# SH_IR_V1_0.net
KiCad netlist of a schematic drawn in Altium Designer
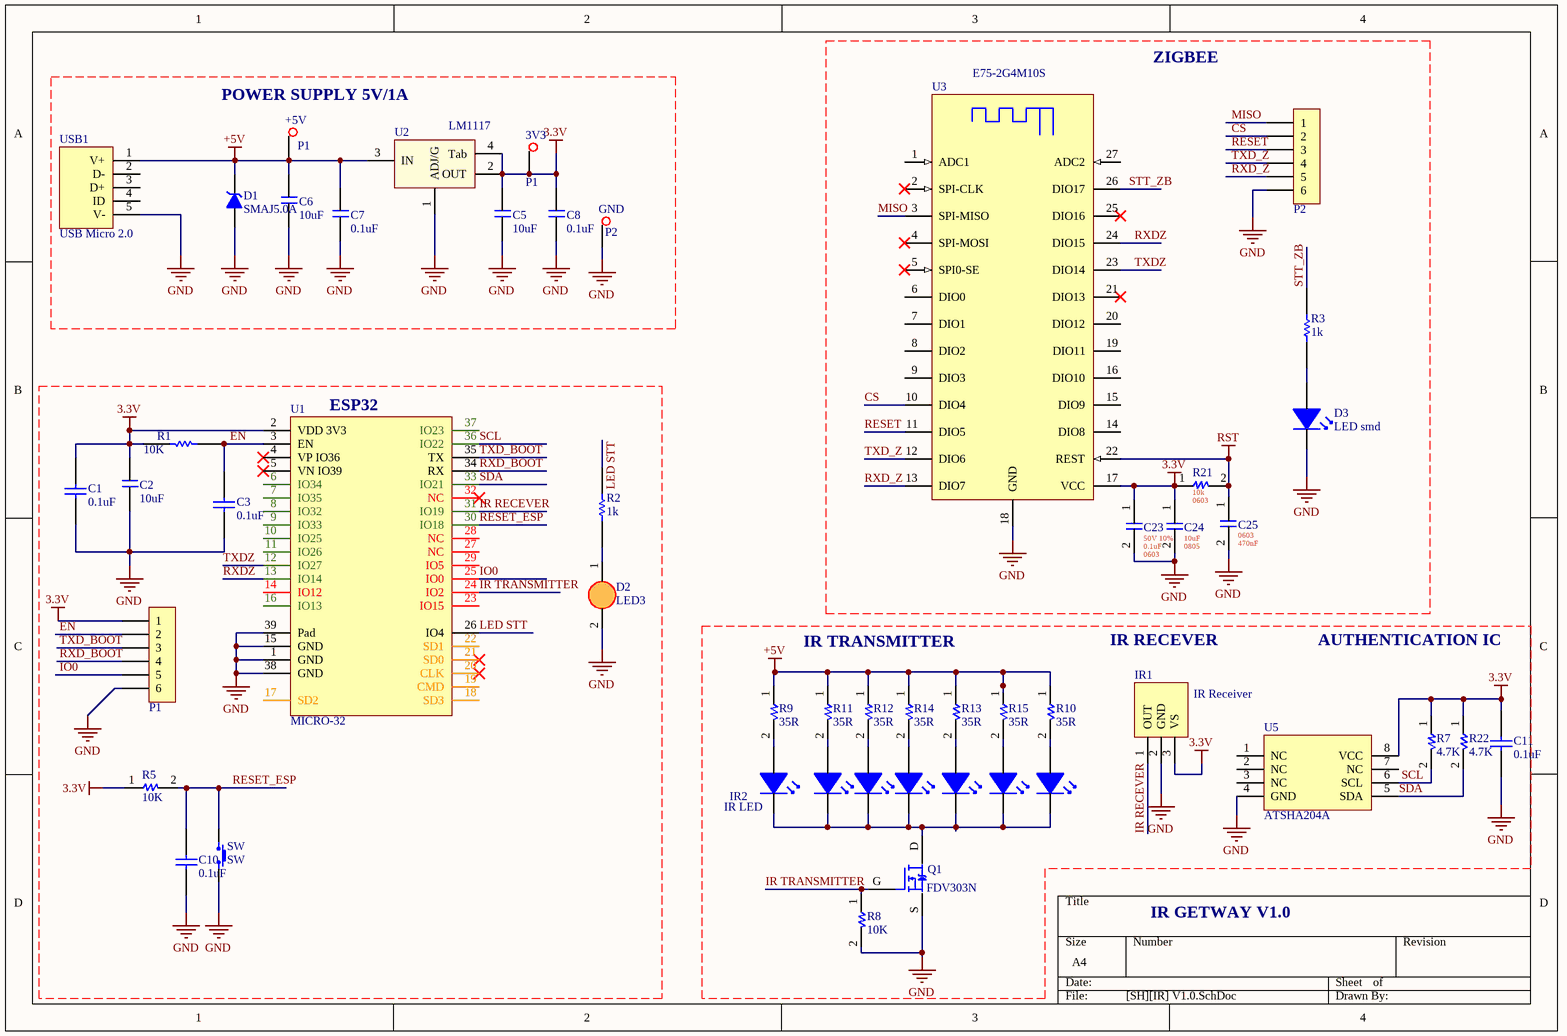
[diagram p0: [SH][IR] V1.0.SchDoc]

(export (version "E")
  (design (tool "Eeschema 10.0.6"))
  (components
    (comp (ref "+5V") (value "P1") (footprint "TEXT_POINT") (libsource (lib "Kienlib") (part "P1")))
    (comp (ref "3V3") (value "P1") (footprint "TEXT_POINT") (libsource (lib "Kienlib") (part "P1")))
    (comp (ref "C1")
      (value "0.1uF")
      (footprint "0603 C")
      (libsource (lib "Library V1.0") (part "CAPACITOR NON POL"))
    )
    (comp (ref "C2") (value "10uF") (footprint "0805 C") (libsource (lib "Kienlib") (part "CAP NOP")))
    (comp (ref "C3")
      (value "0.1uF")
      (footprint "0603 C")
      (libsource (lib "Library V1.0") (part "CAPACITOR NON POL"))
    )
    (comp (ref "C5") (value "10uF") (footprint "0805 C") (libsource (lib "Kienlib") (part "CAP NOP")))
    (comp (ref "C6") (value "10uF") (footprint "0805 C") (libsource (lib "Kienlib") (part "CAP NOP")))
    (comp (ref "C7") (value "0.1uF") (footprint "0603 C") (libsource (lib "Kienlib") (part "CAP NOP")))
    (comp (ref "C8") (value "0.1uF") (footprint "0603 C") (libsource (lib "Kienlib") (part "CAP NOP")))
    (comp (ref "C10")
      (value "0.1uF")
      (footprint "0603 C")
      (libsource (lib "Library V1.0") (part "CAPACITOR NON POL"))
    )
    (comp (ref "C11")
      (value "0.1uF")
      (footprint "0603 C")
      (libsource (lib "Library V1.0") (part "CAPACITOR NON POL"))
    )
    (comp (ref "C23")
      (value "0.1uF")
      (footprint "0603 C")
      (description "CAP CER 0.1uF 50V 10% 0603 SMD")
      (fields
        (field (name "VOLTAGE + TOLE") "50V 10%")
        (field (name "FP") "0603")
        (field (name "CREATOR") "MMUOP")
      )
      (libsource (lib "Capacitor") (part "0603 0.1uF CER"))
    )
    (comp (ref "C24")
      (value "10uF")
      (footprint "0805 C")
      (description "CAP CER 10uF 50V 10% 0805 SMD")
      (fields (field (name "FP") "0805") (field (name "CREATOR") "MMUOP"))
      (libsource (lib "Capacitor") (part "0805 10uF CER"))
    )
    (comp (ref "C25")
      (value "470nF")
      (footprint "0603 C")
      (description "CAP CER 470nF 50V 10% 0603 SMD")
      (fields (field (name "FP") "0603") (field (name "CREATOR") "MMUOP"))
      (libsource (lib "Capacitor") (part "0603 470nF CER"))
    )
    (comp (ref "D1")
      (value "SMAJ5.0A")
      (footprint "DO214AC")
      (fields (field (name "EDITOR") "MMUOP"))
      (libsource (lib "Kienlib") (part "Diode Zener"))
    )
    (comp (ref "D2")
      (value "LED3")
      (footprint "LED3mm")
      (description "LED 3mm")
      (libsource (lib "My Library") (part "LED 3mm"))
    )
    (comp (ref "D3")
      (value "LED smd")
      (footprint "LED0603_1608")
      (libsource (lib "Kienlib") (part "LED smd"))
    )
    (comp (ref "GND") (value "P2") (footprint "TEXT_POINT") (libsource (lib "Kienlib") (part "P1")))
    (comp (ref "IR1")
      (value "IR Receiver")
      (footprint "TSOP1838")
      (libsource (lib "Kienlib") (part "IR Receiver"))
    )
    (comp (ref "IR2") (value "IR LED") (footprint "IR_LED7") (libsource (lib "Kienlib") (part "IR LED")))
    (comp (ref "P1") (value "P6") (footprint "P6 - 1.27MM") (libsource (lib "Kienlib") (part "P6")))
    (comp (ref "P2") (value "P6") (footprint "P6 - 1.27MM") (libsource (lib "Kienlib") (part "P6")))
    (comp (ref "Q1") (value "FDV303N") (footprint "SOT23-3") (libsource (lib "Kienlib") (part "MOSFET - N")))
    (comp (ref "R1") (value "10K") (footprint "0603 R") (libsource (lib "Library V1.0") (part "RESISTOR")))
    (comp (ref "R2") (value "1k") (footprint "0603 R") (libsource (lib "Library V1.0") (part "RESISTOR")))
    (comp (ref "R3") (value "1k") (footprint "0603 R") (libsource (lib "Library V1.0") (part "RESISTOR")))
    (comp (ref "R5") (value "10K") (footprint "0603 R") (libsource (lib "Kienlib") (part "Res SMD")))
    (comp (ref "R7") (value "4.7K") (footprint "0603 R") (libsource (lib "Kienlib") (part "Res SMD")))
    (comp (ref "R8") (value "10K") (footprint "0603 R") (libsource (lib "Kienlib") (part "Res SMD")))
    (comp (ref "R9") (value "35R") (footprint "0603 R") (libsource (lib "Kienlib") (part "Res SMD")))
    (comp (ref "R10") (value "35R") (footprint "0603 R") (libsource (lib "Kienlib") (part "Res SMD")))
    (comp (ref "R11") (value "35R") (footprint "0603 R") (libsource (lib "Kienlib") (part "Res SMD")))
    (comp (ref "R12") (value "35R") (footprint "0603 R") (libsource (lib "Kienlib") (part "Res SMD")))
    (comp (ref "R13") (value "35R") (footprint "0603 R") (libsource (lib "Kienlib") (part "Res SMD")))
    (comp (ref "R14") (value "35R") (footprint "0603 R") (libsource (lib "Kienlib") (part "Res SMD")))
    (comp (ref "R15") (value "35R") (footprint "0603 R") (libsource (lib "Kienlib") (part "Res SMD")))
    (comp (ref "R21")
      (value "10k")
      (footprint "0603 R")
      (description "10k 1% 0603 SMD")
      (fields (field (name "FP") "0603") (field (name "CREATOR") "MMUOP"))
      (libsource (lib "Res") (part "0603 10k 1%"))
    )
    (comp (ref "R22") (value "4.7K") (footprint "0603 R") (libsource (lib "Kienlib") (part "Res SMD")))
    (comp (ref "SW") (value "SW") (footprint "BUTTON 4P") (libsource (lib "Kienlib") (part "SW")))
    (comp (ref "U1")
      (value "MICRO-32")
      (footprint "ESP MICRO 32")
      (libsource (lib "Kienlib") (part "ESP MICRO-32"))
    )
    (comp (ref "U2")
      (value "LM1117")
      (footprint "VioletofSun:SOT223-4N")
      (description "3v3")
      (libsource (lib "VioletofSun") (part "LM1117"))
    )
    (comp (ref "U3")
      (value "E75-2G4M10S")
      (footprint "NXP-E75-10S")
      (libsource (lib "Kienlib") (part "ebyte - E75-2G4M10S"))
    )
    (comp (ref "U5") (value "ATSHA204A") (footprint "SOIC8") (libsource (lib "Kienlib") (part "ATSHA204-A")))
    (comp (ref "USB1")
      (value "USB Micro 2.0")
      (footprint "USB Micro 2.0")
      (libsource (lib "Kienlib") (part "USB Micro 2.0"))
    )
  )
  (nets
    (net (code "1") (name "+5V") (class "Default")
      (node (ref "C6") (pin "2") (pinfunction "2_2") (pintype "passive"))
      (node (ref "C7") (pin "2") (pinfunction "2_2") (pintype "passive"))
      (node (ref "D1") (pin "2") (pinfunction "2_2") (pintype "passive"))
      (node (ref "R10") (pin "1") (pinfunction "1_1") (pintype "passive"))
      (node (ref "R11") (pin "1") (pinfunction "1_1") (pintype "passive"))
      (node (ref "R12") (pin "1") (pinfunction "1_1") (pintype "passive"))
      (node (ref "R13") (pin "1") (pinfunction "1_1") (pintype "passive"))
      (node (ref "R14") (pin "1") (pinfunction "1_1") (pintype "passive"))
      (node (ref "R15") (pin "1") (pinfunction "1_1") (pintype "passive"))
      (node (ref "R9") (pin "1") (pinfunction "1_1") (pintype "passive"))
      (node (ref "U2") (pin "3") (pinfunction "IN_3") (pintype "passive"))
      (node (ref "USB1") (pin "1") (pinfunction "V+_1") (pintype "passive"))
    )
    (net (code "2") (name "/CS") (class "Default")
      (node (ref "P2") (pin "2") (pinfunction "2_2") (pintype "passive"))
      (node (ref "U3") (pin "10") (pinfunction "DIO4_10") (pintype "passive"))
    )
    (net (code "3") (name "/EN") (class "Default")
      (node (ref "C3") (pin "2") (pinfunction "2_2") (pintype "passive"))
      (node (ref "P1") (pin "2") (pinfunction "2_2") (pintype "passive"))
      (node (ref "R1") (pin "1") (pinfunction "1_1") (pintype "passive"))
      (node (ref "U1") (pin "3") (pinfunction "EN_3") (pintype "passive"))
    )
    (net (code "4") (name "/IO0") (class "Default")
      (node (ref "P1") (pin "5") (pinfunction "5_5") (pintype "passive"))
      (node (ref "U1") (pin "25") (pinfunction "IO0_25") (pintype "passive"))
    )
    (net (code "5") (name "/IR RECEVER") (class "Default")
      (node (ref "IR1") (pin "1") (pinfunction "OUT_1") (pintype "passive"))
      (node (ref "U1") (pin "31") (pinfunction "IO19_31") (pintype "passive"))
    )
    (net (code "6") (name "/IR TRANSMITTER") (class "Default")
      (node (ref "Q1") (pin "G") (pinfunction "G_G") (pintype "passive"))
      (node (ref "R8") (pin "1") (pinfunction "1_1") (pintype "passive"))
      (node (ref "U1") (pin "24") (pinfunction "IO2_24") (pintype "passive"))
    )
    (net (code "7") (name "/LED STT") (class "Default")
      (node (ref "R2") (pin "1") (pinfunction "1_1") (pintype "passive"))
      (node (ref "U1") (pin "26") (pinfunction "IO4_26") (pintype "passive"))
    )
    (net (code "8") (name "/MISO") (class "Default")
      (node (ref "P2") (pin "1") (pinfunction "1_1") (pintype "passive"))
      (node (ref "U3") (pin "3") (pinfunction "SPI-MISO_3") (pintype "passive"))
    )
    (net (code "9") (name "/RESET") (class "Default")
      (node (ref "P2") (pin "3") (pinfunction "3_3") (pintype "passive"))
      (node (ref "U3") (pin "11") (pinfunction "DIO5_11") (pintype "passive"))
    )
    (net (code "10") (name "/RESET_ESP") (class "Default")
      (node (ref "C10") (pin "2") (pinfunction "2_2") (pintype "passive"))
      (node (ref "R5") (pin "2") (pinfunction "2_2") (pintype "passive"))
      (node (ref "SW") (pin "1") (pinfunction "1_1") (pintype "passive"))
      (node (ref "U1") (pin "30") (pinfunction "IO18_30") (pintype "passive"))
    )
    (net (code "11") (name "/RXDZ") (class "Default")
      (node (ref "U1") (pin "13") (pinfunction "IO14_13") (pintype "passive"))
      (node (ref "U3") (pin "24") (pinfunction "DIO15_24") (pintype "passive"))
    )
    (net (code "12") (name "/RXD_BOOT") (class "Default")
      (node (ref "P1") (pin "4") (pinfunction "4_4") (pintype "passive"))
      (node (ref "U1") (pin "34") (pinfunction "RX_34") (pintype "passive"))
    )
    (net (code "13") (name "/RXD_Z") (class "Default")
      (node (ref "P2") (pin "5") (pinfunction "5_5") (pintype "passive"))
      (node (ref "U3") (pin "13") (pinfunction "DIO7_13") (pintype "passive"))
    )
    (net (code "14") (name "/SCL") (class "Default")
      (node (ref "R7") (pin "2") (pinfunction "2_2") (pintype "passive"))
      (node (ref "U1") (pin "36") (pinfunction "IO22_36") (pintype "passive"))
      (node (ref "U5") (pin "6") (pinfunction "SCL_6") (pintype "passive"))
    )
    (net (code "15") (name "/SDA") (class "Default")
      (node (ref "R22") (pin "2") (pinfunction "2_2") (pintype "passive"))
      (node (ref "U1") (pin "33") (pinfunction "IO21_33") (pintype "passive"))
      (node (ref "U5") (pin "5") (pinfunction "SDA_5") (pintype "passive"))
    )
    (net (code "16") (name "/STT_ZB") (class "Default")
      (node (ref "R3") (pin "1") (pinfunction "1_1") (pintype "passive"))
      (node (ref "U3") (pin "26") (pinfunction "DIO17_26") (pintype "passive"))
    )
    (net (code "17") (name "/TXDZ") (class "Default")
      (node (ref "U1") (pin "12") (pinfunction "IO27_12") (pintype "passive"))
      (node (ref "U3") (pin "23") (pinfunction "DIO14_23") (pintype "passive"))
    )
    (net (code "18") (name "/TXD_BOOT") (class "Default")
      (node (ref "P1") (pin "3") (pinfunction "3_3") (pintype "passive"))
      (node (ref "U1") (pin "35") (pinfunction "TX_35") (pintype "passive"))
    )
    (net (code "19") (name "/TXD_Z") (class "Default")
      (node (ref "P2") (pin "4") (pinfunction "4_4") (pintype "passive"))
      (node (ref "U3") (pin "12") (pinfunction "DIO6_12") (pintype "passive"))
    )
    (net (code "20") (name "3.3V") (class "Default")
      (node (ref "3V3") (pin "1") (pinfunction "P_1") (pintype "passive"))
      (node (ref "C1") (pin "2") (pinfunction "2_2") (pintype "passive"))
      (node (ref "C11") (pin "2") (pinfunction "2_2") (pintype "passive"))
      (node (ref "C2") (pin "2") (pinfunction "2_2") (pintype "passive"))
      (node (ref "C23") (pin "1") (pinfunction "1_1") (pintype "passive"))
      (node (ref "C24") (pin "1") (pinfunction "1_1") (pintype "passive"))
      (node (ref "C5") (pin "2") (pinfunction "2_2") (pintype "passive"))
      (node (ref "C8") (pin "2") (pinfunction "2_2") (pintype "passive"))
      (node (ref "IR1") (pin "3") (pinfunction "VS_3") (pintype "passive"))
      (node (ref "P1") (pin "1") (pinfunction "1_1") (pintype "passive"))
      (node (ref "R1") (pin "2") (pinfunction "2_2") (pintype "passive"))
      (node (ref "R21") (pin "1") (pinfunction "1_1") (pintype "passive"))
      (node (ref "R22") (pin "1") (pinfunction "1_1") (pintype "passive"))
      (node (ref "R5") (pin "1") (pinfunction "1_1") (pintype "passive"))
      (node (ref "R7") (pin "1") (pinfunction "1_1") (pintype "passive"))
      (node (ref "U1") (pin "2") (pinfunction "VDD_3V3_2") (pintype "passive"))
      (node (ref "U2") (pin "2") (pinfunction "OUT_2") (pintype "passive"))
      (node (ref "U2") (pin "4") (pinfunction "Tab_4") (pintype "passive"))
      (node (ref "U3") (pin "17") (pinfunction "VCC_17") (pintype "passive"))
      (node (ref "U5") (pin "8") (pinfunction "VCC_8") (pintype "passive"))
    )
    (net (code "21") (name "GND") (class "Default")
      (node (ref "C1") (pin "1") (pinfunction "1_1") (pintype "passive"))
      (node (ref "C10") (pin "1") (pinfunction "1_1") (pintype "passive"))
      (node (ref "C11") (pin "1") (pinfunction "1_1") (pintype "passive"))
      (node (ref "C2") (pin "1") (pinfunction "1_1") (pintype "passive"))
      (node (ref "C23") (pin "2") (pinfunction "2_2") (pintype "passive"))
      (node (ref "C24") (pin "2") (pinfunction "2_2") (pintype "passive"))
      (node (ref "C25") (pin "2") (pinfunction "2_2") (pintype "passive"))
      (node (ref "C3") (pin "1") (pinfunction "1_1") (pintype "passive"))
      (node (ref "C5") (pin "1") (pinfunction "1_1") (pintype "passive"))
      (node (ref "C6") (pin "1") (pinfunction "1_1") (pintype "passive"))
      (node (ref "C7") (pin "1") (pinfunction "1_1") (pintype "passive"))
      (node (ref "C8") (pin "1") (pinfunction "1_1") (pintype "passive"))
      (node (ref "D1") (pin "1") (pinfunction "1_1") (pintype "passive"))
      (node (ref "D2") (pin "2") (pinfunction "K_2") (pintype "passive"))
      (node (ref "D3") (pin "2") (pinfunction "2_2") (pintype "passive"))
      (node (ref "GND") (pin "1") (pinfunction "P_1") (pintype "passive"))
      (node (ref "IR1") (pin "2") (pinfunction "GND_2") (pintype "passive"))
      (node (ref "P1") (pin "6") (pinfunction "6_6") (pintype "passive"))
      (node (ref "P2") (pin "6") (pinfunction "6_6") (pintype "passive"))
      (node (ref "Q1") (pin "S") (pinfunction "S_S") (pintype "passive"))
      (node (ref "R8") (pin "2") (pinfunction "2_2") (pintype "passive"))
      (node (ref "SW") (pin "2") (pinfunction "2_2") (pintype "passive"))
      (node (ref "U1") (pin "1") (pinfunction "GND_1") (pintype "passive"))
      (node (ref "U1") (pin "15") (pinfunction "GND_15") (pintype "passive"))
      (node (ref "U1") (pin "38") (pinfunction "GND_38") (pintype "passive"))
      (node (ref "U1") (pin "39") (pinfunction "Pad_39") (pintype "passive"))
      (node (ref "U2") (pin "1") (pinfunction "ADJ/G_1") (pintype "passive"))
      (node (ref "U3") (pin "18") (pinfunction "GND_18") (pintype "passive"))
      (node (ref "U5") (pin "4") (pinfunction "GND_4") (pintype "passive"))
      (node (ref "USB1") (pin "5") (pinfunction "V-_5") (pintype "passive"))
    )
    (net (code "22") (name "Net-(D2-A)") (class "Default")
      (node (ref "D2") (pin "1") (pinfunction "A_1") (pintype "passive"))
      (node (ref "R2") (pin "2") (pinfunction "2_2") (pintype "passive"))
    )
    (net (code "23") (name "Net-(D3-Pad1)") (class "Default")
      (node (ref "D3") (pin "1") (pinfunction "1_1") (pintype "passive"))
      (node (ref "R3") (pin "2") (pinfunction "2_2") (pintype "passive"))
    )
    (net (code "24") (name "Net-(IR2-Pad1)") (class "Default")
      (node (ref "IR2") (pin "1") (pinfunction "1_1") (pintype "passive"))
      (node (ref "R9") (pin "2") (pinfunction "2_2") (pintype "passive"))
    )
    (net (code "25") (name "Net-(IR2-Pad2)") (class "Default")
      (node (ref "IR2") (pin "2") (pinfunction "2_2") (pintype "passive"))
      (node (ref "R11") (pin "2") (pinfunction "2_2") (pintype "passive"))
    )
    (net (code "26") (name "Net-(IR2-Pad3)") (class "Default")
      (node (ref "IR2") (pin "3") (pinfunction "3_3") (pintype "passive"))
      (node (ref "R12") (pin "2") (pinfunction "2_2") (pintype "passive"))
    )
    (net (code "27") (name "Net-(IR2-Pad4)") (class "Default")
      (node (ref "IR2") (pin "4") (pinfunction "4_4") (pintype "passive"))
      (node (ref "R14") (pin "2") (pinfunction "2_2") (pintype "passive"))
    )
    (net (code "28") (name "Net-(IR2-Pad5)") (class "Default")
      (node (ref "IR2") (pin "5") (pinfunction "5_5") (pintype "passive"))
      (node (ref "R13") (pin "2") (pinfunction "2_2") (pintype "passive"))
    )
    (net (code "29") (name "Net-(IR2-Pad6)") (class "Default")
      (node (ref "IR2") (pin "6") (pinfunction "6_6") (pintype "passive"))
      (node (ref "R15") (pin "2") (pinfunction "2_2") (pintype "passive"))
    )
    (net (code "30") (name "Net-(IR2-Pad7)") (class "Default")
      (node (ref "IR2") (pin "7") (pinfunction "7_7") (pintype "passive"))
      (node (ref "R10") (pin "2") (pinfunction "2_2") (pintype "passive"))
    )
    (net (code "31") (name "Net-(IR2-PadK)") (class "Default")
      (node (ref "IR2") (pin "K") (pinfunction "K_K") (pintype "passive"))
      (node (ref "Q1") (pin "D") (pinfunction "D_D") (pintype "passive"))
    )
    (net (code "32") (name "RST") (class "Default")
      (node (ref "C25") (pin "1") (pinfunction "1_1") (pintype "passive"))
      (node (ref "R21") (pin "2") (pinfunction "2_2") (pintype "passive"))
      (node (ref "U3") (pin "22") (pinfunction "REST_22") (pintype "input"))
    )
    (net (code "33") (name "unconnected-(+5V-P-Pad1)") (class "Default")
      (node (ref "+5V") (pin "1") (pinfunction "P_1") (pintype "passive"))
    )
    (net (code "34") (name "unconnected-(U1-CLK-Pad20)") (class "Default")
      (node (ref "U1") (pin "20") (pinfunction "CLK_20") (pintype "passive+no_connect"))
    )
    (net (code "35") (name "unconnected-(U1-CMD-Pad19)") (class "Default")
      (node (ref "U1") (pin "19") (pinfunction "CMD_19") (pintype "passive"))
    )
    (net (code "36") (name "unconnected-(U1-IO5-Pad29)") (class "Default")
      (node (ref "U1") (pin "29") (pinfunction "IO5_29") (pintype "passive"))
    )
    (net (code "37") (name "unconnected-(U1-IO12-Pad14)") (class "Default")
      (node (ref "U1") (pin "14") (pinfunction "IO12_14") (pintype "passive"))
    )
    (net (code "38") (name "unconnected-(U1-IO13-Pad16)") (class "Default")
      (node (ref "U1") (pin "16") (pinfunction "IO13_16") (pintype "passive"))
    )
    (net (code "39") (name "unconnected-(U1-IO15-Pad23)") (class "Default")
      (node (ref "U1") (pin "23") (pinfunction "IO15_23") (pintype "passive"))
    )
    (net (code "40") (name "unconnected-(U1-IO23-Pad37)") (class "Default")
      (node (ref "U1") (pin "37") (pinfunction "IO23_37") (pintype "passive"))
    )
    (net (code "41") (name "unconnected-(U1-IO25-Pad10)") (class "Default")
      (node (ref "U1") (pin "10") (pinfunction "IO25_10") (pintype "passive"))
    )
    (net (code "42") (name "unconnected-(U1-IO26-Pad11)") (class "Default")
      (node (ref "U1") (pin "11") (pinfunction "IO26_11") (pintype "passive"))
    )
    (net (code "43") (name "unconnected-(U1-IO32-Pad8)") (class "Default")
      (node (ref "U1") (pin "8") (pinfunction "IO32_8") (pintype "passive"))
    )
    (net (code "44") (name "unconnected-(U1-IO33-Pad9)") (class "Default")
      (node (ref "U1") (pin "9") (pinfunction "IO33_9") (pintype "passive"))
    )
    (net (code "45") (name "unconnected-(U1-IO34-Pad6)") (class "Default")
      (node (ref "U1") (pin "6") (pinfunction "IO34_6") (pintype "passive"))
    )
    (net (code "46") (name "unconnected-(U1-IO35-Pad7)") (class "Default")
      (node (ref "U1") (pin "7") (pinfunction "IO35_7") (pintype "passive"))
    )
    (net (code "47") (name "unconnected-(U1-NC-Pad27)") (class "Default")
      (node (ref "U1") (pin "27") (pinfunction "NC_27") (pintype "passive"))
    )
    (net (code "48") (name "unconnected-(U1-NC-Pad28)") (class "Default")
      (node (ref "U1") (pin "28") (pinfunction "NC_28") (pintype "passive"))
    )
    (net (code "49") (name "unconnected-(U1-NC-Pad32)") (class "Default")
      (node (ref "U1") (pin "32") (pinfunction "NC_32") (pintype "passive+no_connect"))
    )
    (net (code "50") (name "unconnected-(U1-SD0-Pad21)") (class "Default")
      (node (ref "U1") (pin "21") (pinfunction "SD0_21") (pintype "passive+no_connect"))
    )
    (net (code "51") (name "unconnected-(U1-SD1-Pad22)") (class "Default")
      (node (ref "U1") (pin "22") (pinfunction "SD1_22") (pintype "passive"))
    )
    (net (code "52") (name "unconnected-(U1-SD2-Pad17)") (class "Default")
      (node (ref "U1") (pin "17") (pinfunction "SD2_17") (pintype "passive"))
    )
    (net (code "53") (name "unconnected-(U1-SD3-Pad18)") (class "Default")
      (node (ref "U1") (pin "18") (pinfunction "SD3_18") (pintype "passive"))
    )
    (net (code "54") (name "unconnected-(U1-VN_IO39-Pad5)") (class "Default")
      (node (ref "U1") (pin "5") (pinfunction "VN_IO39_5") (pintype "passive+no_connect"))
    )
    (net (code "55") (name "unconnected-(U1-VP_IO36-Pad4)") (class "Default")
      (node (ref "U1") (pin "4") (pinfunction "VP_IO36_4") (pintype "passive+no_connect"))
    )
    (net (code "56") (name "unconnected-(U3-ADC1-Pad1)") (class "Default")
      (node (ref "U3") (pin "1") (pinfunction "ADC1_1") (pintype "input"))
    )
    (net (code "57") (name "unconnected-(U3-ADC2-Pad27)") (class "Default")
      (node (ref "U3") (pin "27") (pinfunction "ADC2_27") (pintype "input"))
    )
    (net (code "58") (name "unconnected-(U3-DIO0-Pad6)") (class "Default")
      (node (ref "U3") (pin "6") (pinfunction "DIO0_6") (pintype "passive"))
    )
    (net (code "59") (name "unconnected-(U3-DIO1-Pad7)") (class "Default")
      (node (ref "U3") (pin "7") (pinfunction "DIO1_7") (pintype "passive"))
    )
    (net (code "60") (name "unconnected-(U3-DIO2-Pad8)") (class "Default")
      (node (ref "U3") (pin "8") (pinfunction "DIO2_8") (pintype "passive"))
    )
    (net (code "61") (name "unconnected-(U3-DIO3-Pad9)") (class "Default")
      (node (ref "U3") (pin "9") (pinfunction "DIO3_9") (pintype "passive"))
    )
    (net (code "62") (name "unconnected-(U3-DIO8-Pad14)") (class "Default")
      (node (ref "U3") (pin "14") (pinfunction "DIO8_14") (pintype "passive"))
    )
    (net (code "63") (name "unconnected-(U3-DIO9-Pad15)") (class "Default")
      (node (ref "U3") (pin "15") (pinfunction "DIO9_15") (pintype "passive"))
    )
    (net (code "64") (name "unconnected-(U3-DIO10-Pad16)") (class "Default")
      (node (ref "U3") (pin "16") (pinfunction "DIO10_16") (pintype "passive"))
    )
    (net (code "65") (name "unconnected-(U3-DIO11-Pad19)") (class "Default")
      (node (ref "U3") (pin "19") (pinfunction "DIO11_19") (pintype "passive"))
    )
    (net (code "66") (name "unconnected-(U3-DIO12-Pad20)") (class "Default")
      (node (ref "U3") (pin "20") (pinfunction "DIO12_20") (pintype "passive"))
    )
    (net (code "67") (name "unconnected-(U3-DIO13-Pad21)") (class "Default")
      (node (ref "U3") (pin "21") (pinfunction "DIO13_21") (pintype "passive+no_connect"))
    )
    (net (code "68") (name "unconnected-(U3-DIO16-Pad25)") (class "Default")
      (node (ref "U3") (pin "25") (pinfunction "DIO16_25") (pintype "passive+no_connect"))
    )
    (net (code "69") (name "unconnected-(U3-SPI-CLK-Pad2)") (class "Default")
      (node (ref "U3") (pin "2") (pinfunction "SPI-CLK_2") (pintype "input+no_connect"))
    )
    (net (code "70") (name "unconnected-(U3-SPI-MOSI-Pad4)") (class "Default")
      (node (ref "U3") (pin "4") (pinfunction "SPI-MOSI_4") (pintype "passive+no_connect"))
    )
    (net (code "71") (name "unconnected-(U3-SPI0-SE-Pad5)") (class "Default")
      (node (ref "U3") (pin "5") (pinfunction "SPI0-SE_5") (pintype "input+no_connect"))
    )
    (net (code "72") (name "unconnected-(U5-NC-Pad1)") (class "Default")
      (node (ref "U5") (pin "1") (pinfunction "NC_1") (pintype "passive"))
    )
    (net (code "73") (name "unconnected-(U5-NC-Pad2)") (class "Default")
      (node (ref "U5") (pin "2") (pinfunction "NC_2") (pintype "passive"))
    )
    (net (code "74") (name "unconnected-(U5-NC-Pad3)") (class "Default")
      (node (ref "U5") (pin "3") (pinfunction "NC_3") (pintype "passive"))
    )
    (net (code "75") (name "unconnected-(U5-NC-Pad7)") (class "Default")
      (node (ref "U5") (pin "7") (pinfunction "NC_7") (pintype "passive"))
    )
    (net (code "76") (name "unconnected-(USB1-D+-Pad3)") (class "Default")
      (node (ref "USB1") (pin "3") (pinfunction "D+_3") (pintype "passive"))
    )
    (net (code "77") (name "unconnected-(USB1-D--Pad2)") (class "Default")
      (node (ref "USB1") (pin "2") (pinfunction "D-_2") (pintype "passive"))
    )
    (net (code "78") (name "unconnected-(USB1-ID-Pad4)") (class "Default")
      (node (ref "USB1") (pin "4") (pinfunction "ID_4") (pintype "passive"))
    )
  )
)
